# lcd13264-shield.net
KiCad netlist of a schematic drawn in EAGLE
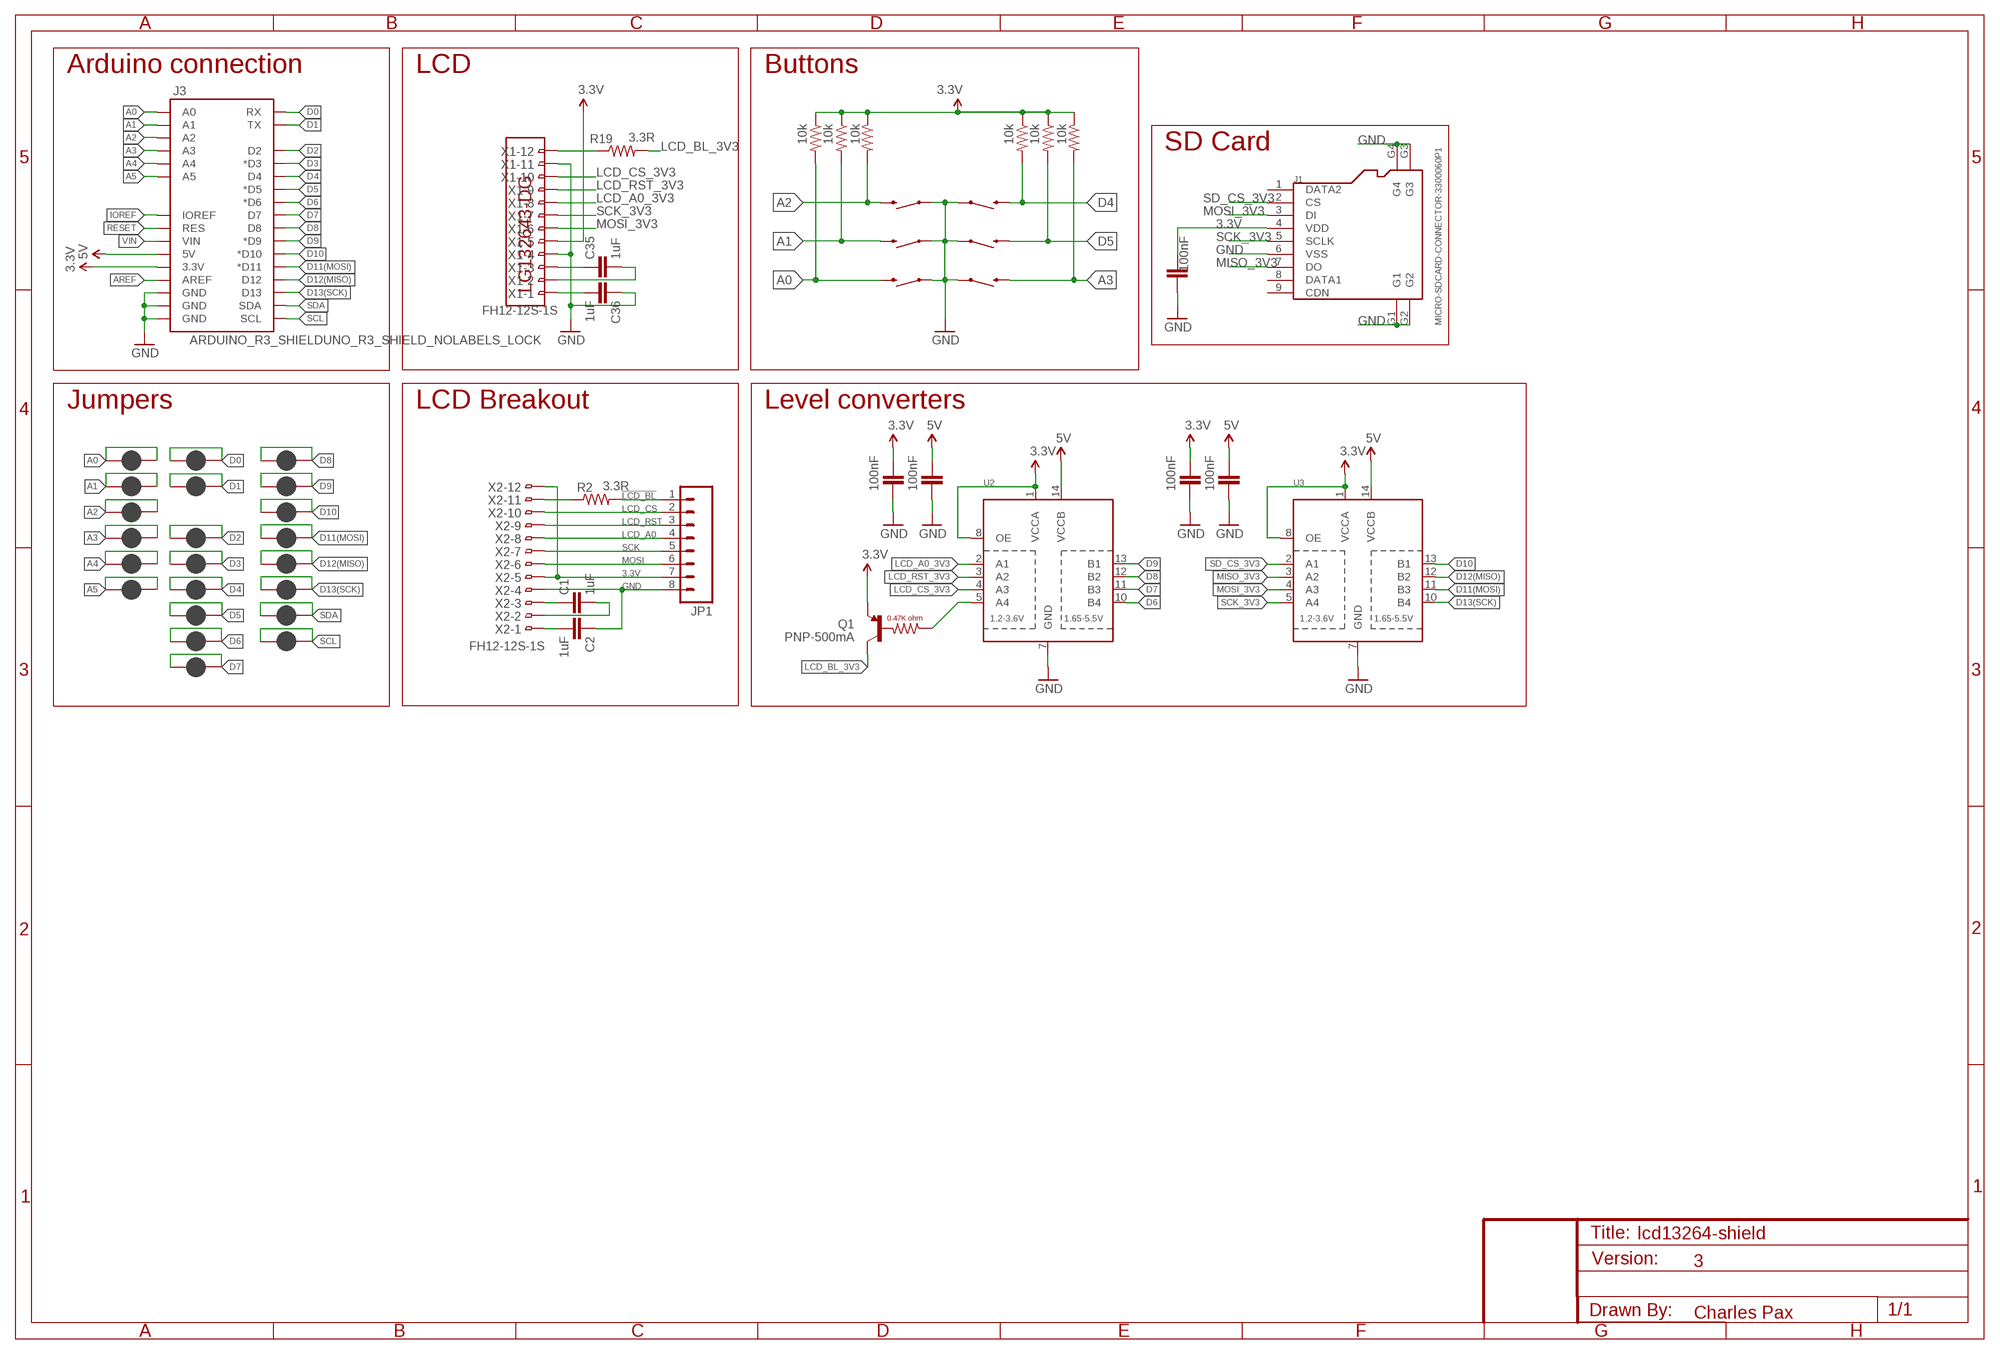
[diagram p0: schematic, sheet 1]

(export (version "E")
  (design (tool "Eeschema 10.0.6"))
  (components
    (comp (ref "C1")
      (value "1uF")
      (footprint "eagle-import:SPARKFUN-CAPACITORS_0603-CAP")
      (fields (field (name "MPN") "LMK107B7105KA-T"))
      (libsource (lib "eagle-import") (part "SPARKFUN-CAPACITORS_CAP0603-CAP"))
    )
    (comp (ref "C2")
      (value "1uF")
      (footprint "eagle-import:SPARKFUN-CAPACITORS_0603-CAP")
      (fields (field (name "MPN") "LMK107B7105KA-T"))
      (libsource (lib "eagle-import") (part "SPARKFUN-CAPACITORS_CAP0603-CAP"))
    )
    (comp (ref "C3")
      (value "100nF")
      (footprint "eagle-import:SPARKFUN-CAPACITORS_0603-CAP")
      (fields (field (name "MPN") "CL10B104KO8NNNC"))
      (libsource (lib "eagle-import") (part "SPARKFUN-CAPACITORS_CAP0603-CAP"))
    )
    (comp (ref "C4")
      (value "100nF")
      (footprint "eagle-import:SPARKFUN-CAPACITORS_0603-CAP")
      (fields (field (name "MPN") "CL10B104KO8NNNC"))
      (libsource (lib "eagle-import") (part "SPARKFUN-CAPACITORS_CAP0603-CAP"))
    )
    (comp (ref "C5")
      (value "100nF")
      (footprint "eagle-import:SPARKFUN-CAPACITORS_0603-CAP")
      (fields (field (name "MPN") "CL10B104KO8NNNC"))
      (libsource (lib "eagle-import") (part "SPARKFUN-CAPACITORS_CAP0603-CAP"))
    )
    (comp (ref "C6")
      (value "100nF")
      (footprint "eagle-import:SPARKFUN-CAPACITORS_0603-CAP")
      (fields (field (name "MPN") "CL10B104KO8NNNC"))
      (libsource (lib "eagle-import") (part "SPARKFUN-CAPACITORS_CAP0603-CAP"))
    )
    (comp (ref "C21")
      (value "100nF")
      (footprint "eagle-import:SPARKFUN-CAPACITORS_0603-CAP")
      (fields (field (name "MPN") "CL10B104KO8NNNC"))
      (libsource (lib "eagle-import") (part "SPARKFUN-CAPACITORS_CAP0603-CAP"))
    )
    (comp (ref "C35")
      (value "1uF")
      (footprint "eagle-import:SPARKFUN-CAPACITORS_0603-CAP")
      (fields (field (name "MPN") "LMK107B7105KA-T"))
      (libsource (lib "eagle-import") (part "SPARKFUN-CAPACITORS_CAP0603-CAP"))
    )
    (comp (ref "C36")
      (value "1uF")
      (footprint "eagle-import:SPARKFUN-CAPACITORS_0603-CAP")
      (fields (field (name "MPN") "LMK107B7105KA-T"))
      (libsource (lib "eagle-import") (part "SPARKFUN-CAPACITORS_CAP0603-CAP"))
    )
    (comp (ref "J1")
      (value "MICRO-SDCARD-CONNECTOR-3300060P1")
      (footprint "eagle-import:9P-SMD-W-RING")
      (libsource (lib "eagle-import") (part "MICRO-SDCARD-CONNECTOR-3300060P1"))
    )
    (comp (ref "J3")
      (value "ARDUINO_R3_SHIELDUNO_R3_SHIELD_NOLABELS_LOCK")
      (footprint "eagle-import:UNO_R3_SHIELD_NOLABELS_LOCK")
      (libsource (lib "eagle-import") (part "ARDUINO_R3_SHIELDUNO_R3_SHIELD_NOLABELS_LOCK"))
    )
    (comp (ref "JP1")
      (value "M08")
      (footprint "eagle-import:1X08_ROUND")
      (libsource (lib "eagle-import") (part "M08"))
    )
    (comp (ref "Q1")
      (value "PNP-500mA")
      (footprint "eagle-import:SOT23-3")
      (fields (field (name "MPN") "DDTB142TC"))
      (libsource (lib "eagle-import") (part "TRANSISTOR-PNP-DDTB142TC"))
    )
    (comp (ref "R1")
      (value "10k")
      (footprint "eagle-import:SPARKFUN-RESISTORS_0603-RES")
      (fields (field (name "MPN") "RC1608J103CS"))
      (libsource (lib "eagle-import") (part "SPARKFUN-RESISTORS_RESISTOR0603-RES"))
    )
    (comp (ref "R2")
      (value "3.3R")
      (footprint "eagle-import:SPARKFUN-RESISTORS_0603-RES")
      (libsource (lib "eagle-import") (part "SPARKFUN-RESISTORS_RESISTOR0603-RES"))
    )
    (comp (ref "R8")
      (value "10k")
      (footprint "eagle-import:SPARKFUN-RESISTORS_0603-RES")
      (fields (field (name "MPN") "RC1608J103CS"))
      (libsource (lib "eagle-import") (part "SPARKFUN-RESISTORS_RESISTOR0603-RES"))
    )
    (comp (ref "R11")
      (value "10k")
      (footprint "eagle-import:SPARKFUN-RESISTORS_0603-RES")
      (fields (field (name "MPN") "RC1608J103CS"))
      (libsource (lib "eagle-import") (part "SPARKFUN-RESISTORS_RESISTOR0603-RES"))
    )
    (comp (ref "R12")
      (value "10k")
      (footprint "eagle-import:SPARKFUN-RESISTORS_0603-RES")
      (fields (field (name "MPN") "RC1608J103CS"))
      (libsource (lib "eagle-import") (part "SPARKFUN-RESISTORS_RESISTOR0603-RES"))
    )
    (comp (ref "R15")
      (value "10k")
      (footprint "eagle-import:SPARKFUN-RESISTORS_0603-RES")
      (fields (field (name "MPN") "RC1608J103CS"))
      (libsource (lib "eagle-import") (part "SPARKFUN-RESISTORS_RESISTOR0603-RES"))
    )
    (comp (ref "R16")
      (value "10k")
      (footprint "eagle-import:SPARKFUN-RESISTORS_0603-RES")
      (fields (field (name "MPN") "RC1608J103CS"))
      (libsource (lib "eagle-import") (part "SPARKFUN-RESISTORS_RESISTOR0603-RES"))
    )
    (comp (ref "R19")
      (value "3.3R")
      (footprint "eagle-import:SPARKFUN-RESISTORS_0603-RES")
      (libsource (lib "eagle-import") (part "SPARKFUN-RESISTORS_RESISTOR0603-RES"))
    )
    (comp (ref "S1")
      (value "SWITCH-MOMENTARY-2SMD")
      (footprint "eagle-import:TACTILE_SWITCH_SMD")
      (libsource (lib "eagle-import") (part "SWITCH-MOMENTARY-2SMD"))
    )
    (comp (ref "S2")
      (value "SWITCH-MOMENTARY-2SMD")
      (footprint "eagle-import:TACTILE_SWITCH_SMD")
      (libsource (lib "eagle-import") (part "SWITCH-MOMENTARY-2SMD"))
    )
    (comp (ref "S3")
      (value "SWITCH-MOMENTARY-2SMD")
      (footprint "eagle-import:TACTILE_SWITCH_SMD")
      (libsource (lib "eagle-import") (part "SWITCH-MOMENTARY-2SMD"))
    )
    (comp (ref "S4")
      (value "SWITCH-MOMENTARY-2SMD")
      (footprint "eagle-import:TACTILE_SWITCH_SMD")
      (libsource (lib "eagle-import") (part "SWITCH-MOMENTARY-2SMD"))
    )
    (comp (ref "S5")
      (value "SWITCH-MOMENTARY-2SMD")
      (footprint "eagle-import:TACTILE_SWITCH_SMD")
      (libsource (lib "eagle-import") (part "SWITCH-MOMENTARY-2SMD"))
    )
    (comp (ref "S6")
      (value "SWITCH-MOMENTARY-2SMD")
      (footprint "eagle-import:TACTILE_SWITCH_SMD")
      (libsource (lib "eagle-import") (part "SWITCH-MOMENTARY-2SMD"))
    )
    (comp (ref "SJ1")
      (value "JUMPER-PAD-2-NC_BY_PASTE")
      (footprint "eagle-import:PAD-JUMPER-2-NC_BY_PASTE_YES_SILK")
      (libsource (lib "eagle-import") (part "JUMPER-PAD-2-NC_BY_PASTE"))
    )
    (comp (ref "SJ2")
      (value "JUMPER-PAD-2-NC_BY_PASTE")
      (footprint "eagle-import:PAD-JUMPER-2-NC_BY_PASTE_YES_SILK")
      (libsource (lib "eagle-import") (part "JUMPER-PAD-2-NC_BY_PASTE"))
    )
    (comp (ref "SJ3")
      (value "JUMPER-PAD-2-NC_BY_PASTE")
      (footprint "eagle-import:PAD-JUMPER-2-NC_BY_PASTE_YES_SILK")
      (libsource (lib "eagle-import") (part "JUMPER-PAD-2-NC_BY_PASTE"))
    )
    (comp (ref "SJ4")
      (value "JUMPER-PAD-2-NC_BY_PASTE")
      (footprint "eagle-import:PAD-JUMPER-2-NC_BY_PASTE_YES_SILK")
      (libsource (lib "eagle-import") (part "JUMPER-PAD-2-NC_BY_PASTE"))
    )
    (comp (ref "SJ5")
      (value "JUMPER-PAD-2-NC_BY_PASTE")
      (footprint "eagle-import:PAD-JUMPER-2-NC_BY_PASTE_YES_SILK")
      (libsource (lib "eagle-import") (part "JUMPER-PAD-2-NC_BY_PASTE"))
    )
    (comp (ref "SJ6")
      (value "JUMPER-PAD-2-NC_BY_PASTE")
      (footprint "eagle-import:PAD-JUMPER-2-NC_BY_PASTE_YES_SILK")
      (libsource (lib "eagle-import") (part "JUMPER-PAD-2-NC_BY_PASTE"))
    )
    (comp (ref "SJ7")
      (value "JUMPER-PAD-2-NC_BY_PASTE")
      (footprint "eagle-import:PAD-JUMPER-2-NC_BY_PASTE_YES_SILK")
      (libsource (lib "eagle-import") (part "JUMPER-PAD-2-NC_BY_PASTE"))
    )
    (comp (ref "SJ8")
      (value "JUMPER-PAD-2-NC_BY_PASTE")
      (footprint "eagle-import:PAD-JUMPER-2-NC_BY_PASTE_YES_SILK")
      (libsource (lib "eagle-import") (part "JUMPER-PAD-2-NC_BY_PASTE"))
    )
    (comp (ref "SJ9")
      (value "JUMPER-PAD-2-NC_BY_PASTE")
      (footprint "eagle-import:PAD-JUMPER-2-NC_BY_PASTE_YES_SILK")
      (libsource (lib "eagle-import") (part "JUMPER-PAD-2-NC_BY_PASTE"))
    )
    (comp (ref "SJ10")
      (value "JUMPER-PAD-2-NC_BY_PASTE")
      (footprint "eagle-import:PAD-JUMPER-2-NC_BY_PASTE_YES_SILK")
      (libsource (lib "eagle-import") (part "JUMPER-PAD-2-NC_BY_PASTE"))
    )
    (comp (ref "SJ11")
      (value "JUMPER-PAD-2-NC_BY_PASTE")
      (footprint "eagle-import:PAD-JUMPER-2-NC_BY_PASTE_YES_SILK")
      (libsource (lib "eagle-import") (part "JUMPER-PAD-2-NC_BY_PASTE"))
    )
    (comp (ref "SJ12")
      (value "JUMPER-PAD-2-NC_BY_PASTE")
      (footprint "eagle-import:PAD-JUMPER-2-NC_BY_PASTE_YES_SILK")
      (libsource (lib "eagle-import") (part "JUMPER-PAD-2-NC_BY_PASTE"))
    )
    (comp (ref "SJ13")
      (value "JUMPER-PAD-2-NC_BY_PASTE")
      (footprint "eagle-import:PAD-JUMPER-2-NC_BY_PASTE_YES_SILK")
      (libsource (lib "eagle-import") (part "JUMPER-PAD-2-NC_BY_PASTE"))
    )
    (comp (ref "SJ14")
      (value "JUMPER-PAD-2-NC_BY_PASTE")
      (footprint "eagle-import:PAD-JUMPER-2-NC_BY_PASTE_YES_SILK")
      (libsource (lib "eagle-import") (part "JUMPER-PAD-2-NC_BY_PASTE"))
    )
    (comp (ref "SJ19")
      (value "JUMPER-PAD-2-NC_BY_PASTE")
      (footprint "eagle-import:PAD-JUMPER-2-NC_BY_PASTE_YES_SILK")
      (libsource (lib "eagle-import") (part "JUMPER-PAD-2-NC_BY_PASTE"))
    )
    (comp (ref "SJ20")
      (value "JUMPER-PAD-2-NC_BY_PASTE")
      (footprint "eagle-import:PAD-JUMPER-2-NC_BY_PASTE_YES_SILK")
      (libsource (lib "eagle-import") (part "JUMPER-PAD-2-NC_BY_PASTE"))
    )
    (comp (ref "SJ21")
      (value "JUMPER-PAD-2-NC_BY_PASTE")
      (footprint "eagle-import:PAD-JUMPER-2-NC_BY_PASTE_YES_SILK")
      (libsource (lib "eagle-import") (part "JUMPER-PAD-2-NC_BY_PASTE"))
    )
    (comp (ref "SJ22")
      (value "JUMPER-PAD-2-NC_BY_PASTE")
      (footprint "eagle-import:PAD-JUMPER-2-NC_BY_PASTE_YES_SILK")
      (libsource (lib "eagle-import") (part "JUMPER-PAD-2-NC_BY_PASTE"))
    )
    (comp (ref "SJ23")
      (value "JUMPER-PAD-2-NC_BY_PASTE")
      (footprint "eagle-import:PAD-JUMPER-2-NC_BY_PASTE_YES_SILK")
      (libsource (lib "eagle-import") (part "JUMPER-PAD-2-NC_BY_PASTE"))
    )
    (comp (ref "SJ24")
      (value "JUMPER-PAD-2-NC_BY_PASTE")
      (footprint "eagle-import:PAD-JUMPER-2-NC_BY_PASTE_YES_SILK")
      (libsource (lib "eagle-import") (part "JUMPER-PAD-2-NC_BY_PASTE"))
    )
    (comp (ref "SJ25")
      (value "JUMPER-PAD-2-NC_BY_PASTE")
      (footprint "eagle-import:PAD-JUMPER-2-NC_BY_PASTE_YES_SILK")
      (libsource (lib "eagle-import") (part "JUMPER-PAD-2-NC_BY_PASTE"))
    )
    (comp (ref "SJ26")
      (value "JUMPER-PAD-2-NC_BY_PASTE")
      (footprint "eagle-import:PAD-JUMPER-2-NC_BY_PASTE_YES_SILK")
      (libsource (lib "eagle-import") (part "JUMPER-PAD-2-NC_BY_PASTE"))
    )
    (comp (ref "U$5")
      (value "LG132643-DG")
      (footprint "eagle-import:LG132643-DG")
      (fields (field (name "MPN") "LG132643-DW"))
      (libsource (lib "eagle-import") (part "LG132643-DG"))
    )
    (comp (ref "U2")
      (value "TXB0104PWRSOIC14")
      (footprint "eagle-import:SO14")
      (fields (field (name "MPN") "TXB0104DR"))
      (libsource (lib "eagle-import") (part "TXB0104PWRSOIC14"))
    )
    (comp (ref "U3")
      (value "TXB0104PWRSOIC14")
      (footprint "eagle-import:SO14")
      (fields (field (name "MPN") "TXB0104DR"))
      (libsource (lib "eagle-import") (part "TXB0104PWRSOIC14"))
    )
    (comp (ref "X1")
      (value "FH12-12S-1S")
      (footprint "eagle-import:FH12-12S-1SH")
      (libsource (lib "eagle-import") (part "FH12-12S-1S"))
    )
    (comp (ref "X2")
      (value "FH12-12S-1S")
      (footprint "eagle-import:FH12-12S-1SH")
      (libsource (lib "eagle-import") (part "FH12-12S-1S"))
    )
  )
  (nets
    (net (code "1") (name "3.3V") (class "Default")
      (node (ref "C21") (pin "2") (pinfunction "2_2") (pintype "passive"))
      (node (ref "C3") (pin "2") (pinfunction "2_2") (pintype "passive"))
      (node (ref "C5") (pin "2") (pinfunction "2_2") (pintype "passive"))
      (node (ref "J1") (pin "4") (pinfunction "VDD_4") (pintype "bidirectional"))
      (node (ref "J3") (pin "3.3V") (pinfunction "3.3V_3.3V") (pintype "bidirectional"))
      (node (ref "Q1") (pin "2") (pinfunction "E_2") (pintype "passive"))
      (node (ref "R1") (pin "1") (pinfunction "1_1") (pintype "passive"))
      (node (ref "R11") (pin "1") (pinfunction "1_1") (pintype "passive"))
      (node (ref "R12") (pin "1") (pinfunction "1_1") (pintype "passive"))
      (node (ref "R15") (pin "1") (pinfunction "1_1") (pintype "passive"))
      (node (ref "R16") (pin "1") (pinfunction "1_1") (pintype "passive"))
      (node (ref "R8") (pin "1") (pinfunction "1_1") (pintype "passive"))
      (node (ref "U2") (pin "1") (pinfunction "VCCA_1") (pintype "bidirectional"))
      (node (ref "U2") (pin "8") (pinfunction "OE_8") (pintype "bidirectional"))
      (node (ref "U3") (pin "1") (pinfunction "VCCA_1") (pintype "bidirectional"))
      (node (ref "U3") (pin "8") (pinfunction "OE_8") (pintype "bidirectional"))
      (node (ref "X1") (pin "5") (pinfunction "1_5") (pintype "passive"))
    )
    (net (code "2") (name "5V") (class "Default")
      (node (ref "C4") (pin "2") (pinfunction "2_2") (pintype "passive"))
      (node (ref "C6") (pin "2") (pinfunction "2_2") (pintype "passive"))
      (node (ref "J3") (pin "5V") (pinfunction "5V_5V") (pintype "bidirectional"))
      (node (ref "U2") (pin "14") (pinfunction "VCCB_14") (pintype "bidirectional"))
      (node (ref "U3") (pin "14") (pinfunction "VCCB_14") (pintype "bidirectional"))
    )
    (net (code "3") (name "A0") (class "Default")
      (node (ref "J3") (pin "A0") (pinfunction "A0_A0") (pintype "bidirectional"))
      (node (ref "R1") (pin "2") (pinfunction "2_2") (pintype "passive"))
      (node (ref "S6") (pin "3") (pinfunction "2_3") (pintype "passive"))
      (node (ref "SJ10") (pin "1") (pinfunction "1_1") (pintype "passive"))
      (node (ref "SJ10") (pin "2") (pinfunction "2_2") (pintype "passive"))
    )
    (net (code "4") (name "A1") (class "Default")
      (node (ref "J3") (pin "A1") (pinfunction "A1_A1") (pintype "bidirectional"))
      (node (ref "R16") (pin "2") (pinfunction "2_2") (pintype "passive"))
      (node (ref "S5") (pin "3") (pinfunction "2_3") (pintype "passive"))
      (node (ref "SJ7") (pin "1") (pinfunction "1_1") (pintype "passive"))
      (node (ref "SJ7") (pin "2") (pinfunction "2_2") (pintype "passive"))
    )
    (net (code "5") (name "A2") (class "Default")
      (node (ref "J3") (pin "A2") (pinfunction "A2_A2") (pintype "bidirectional"))
      (node (ref "R15") (pin "2") (pinfunction "2_2") (pintype "passive"))
      (node (ref "S4") (pin "3") (pinfunction "2_3") (pintype "passive"))
      (node (ref "SJ11") (pin "1") (pinfunction "1_1") (pintype "passive"))
      (node (ref "SJ11") (pin "2") (pinfunction "2_2") (pintype "passive"))
    )
    (net (code "6") (name "A3") (class "Default")
      (node (ref "J3") (pin "A3") (pinfunction "A3_A3") (pintype "bidirectional"))
      (node (ref "R12") (pin "2") (pinfunction "2_2") (pintype "passive"))
      (node (ref "S1") (pin "3") (pinfunction "2_3") (pintype "passive"))
      (node (ref "SJ12") (pin "1") (pinfunction "1_1") (pintype "passive"))
      (node (ref "SJ12") (pin "2") (pinfunction "2_2") (pintype "passive"))
    )
    (net (code "7") (name "A4") (class "Default")
      (node (ref "J3") (pin "A4") (pinfunction "A4_A4") (pintype "bidirectional"))
      (node (ref "SJ13") (pin "1") (pinfunction "1_1") (pintype "passive"))
      (node (ref "SJ13") (pin "2") (pinfunction "2_2") (pintype "passive"))
    )
    (net (code "8") (name "A5") (class "Default")
      (node (ref "J3") (pin "A5") (pinfunction "A5_A5") (pintype "bidirectional"))
      (node (ref "SJ14") (pin "1") (pinfunction "1_1") (pintype "passive"))
      (node (ref "SJ14") (pin "2") (pinfunction "2_2") (pintype "passive"))
    )
    (net (code "9") (name "AREF") (class "Default")
      (node (ref "J3") (pin "AREF") (pinfunction "AREF_AREF") (pintype "bidirectional"))
    )
    (net (code "10") (name "D0") (class "Default")
      (node (ref "J3") (pin "RX") (pinfunction "RX_RX") (pintype "bidirectional"))
      (node (ref "SJ8") (pin "1") (pinfunction "1_1") (pintype "passive"))
      (node (ref "SJ8") (pin "2") (pinfunction "2_2") (pintype "passive"))
    )
    (net (code "11") (name "D1") (class "Default")
      (node (ref "J3") (pin "TX") (pinfunction "TX_TX") (pintype "bidirectional"))
      (node (ref "SJ9") (pin "1") (pinfunction "1_1") (pintype "passive"))
      (node (ref "SJ9") (pin "2") (pinfunction "2_2") (pintype "passive"))
    )
    (net (code "12") (name "D2") (class "Default")
      (node (ref "J3") (pin "D2") (pinfunction "D2_D2") (pintype "bidirectional"))
      (node (ref "SJ3") (pin "1") (pinfunction "1_1") (pintype "passive"))
      (node (ref "SJ3") (pin "2") (pinfunction "2_2") (pintype "passive"))
    )
    (net (code "13") (name "D3") (class "Default")
      (node (ref "J3") (pin "D3") (pinfunction "*D3_D3") (pintype "bidirectional"))
      (node (ref "SJ4") (pin "1") (pinfunction "1_1") (pintype "passive"))
      (node (ref "SJ4") (pin "2") (pinfunction "2_2") (pintype "passive"))
    )
    (net (code "14") (name "D4") (class "Default")
      (node (ref "J3") (pin "D4") (pinfunction "D4_D4") (pintype "bidirectional"))
      (node (ref "R8") (pin "2") (pinfunction "2_2") (pintype "passive"))
      (node (ref "S3") (pin "3") (pinfunction "2_3") (pintype "passive"))
      (node (ref "SJ5") (pin "1") (pinfunction "1_1") (pintype "passive"))
      (node (ref "SJ5") (pin "2") (pinfunction "2_2") (pintype "passive"))
    )
    (net (code "15") (name "D5") (class "Default")
      (node (ref "J3") (pin "D5") (pinfunction "*D5_D5") (pintype "bidirectional"))
      (node (ref "R11") (pin "2") (pinfunction "2_2") (pintype "passive"))
      (node (ref "S2") (pin "3") (pinfunction "2_3") (pintype "passive"))
      (node (ref "SJ6") (pin "1") (pinfunction "1_1") (pintype "passive"))
      (node (ref "SJ6") (pin "2") (pinfunction "2_2") (pintype "passive"))
    )
    (net (code "16") (name "D6") (class "Default")
      (node (ref "J3") (pin "D6") (pinfunction "*D6_D6") (pintype "bidirectional"))
      (node (ref "SJ19") (pin "1") (pinfunction "1_1") (pintype "passive"))
      (node (ref "SJ19") (pin "2") (pinfunction "2_2") (pintype "passive"))
      (node (ref "U2") (pin "10") (pinfunction "B4_10") (pintype "bidirectional"))
    )
    (net (code "17") (name "D7") (class "Default")
      (node (ref "J3") (pin "D7") (pinfunction "D7_D7") (pintype "bidirectional"))
      (node (ref "SJ20") (pin "1") (pinfunction "1_1") (pintype "passive"))
      (node (ref "SJ20") (pin "2") (pinfunction "2_2") (pintype "passive"))
      (node (ref "U2") (pin "11") (pinfunction "B3_11") (pintype "bidirectional"))
    )
    (net (code "18") (name "D8") (class "Default")
      (node (ref "J3") (pin "D8") (pinfunction "D8_D8") (pintype "bidirectional"))
      (node (ref "SJ21") (pin "1") (pinfunction "1_1") (pintype "passive"))
      (node (ref "SJ21") (pin "2") (pinfunction "2_2") (pintype "passive"))
      (node (ref "U2") (pin "12") (pinfunction "B2_12") (pintype "bidirectional"))
    )
    (net (code "19") (name "D9") (class "Default")
      (node (ref "J3") (pin "D9") (pinfunction "*D9_D9") (pintype "bidirectional"))
      (node (ref "SJ22") (pin "1") (pinfunction "1_1") (pintype "passive"))
      (node (ref "SJ22") (pin "2") (pinfunction "2_2") (pintype "passive"))
      (node (ref "U2") (pin "13") (pinfunction "B1_13") (pintype "bidirectional"))
    )
    (net (code "20") (name "D10") (class "Default")
      (node (ref "J3") (pin "D10") (pinfunction "*D10_D10") (pintype "bidirectional"))
      (node (ref "SJ23") (pin "1") (pinfunction "1_1") (pintype "passive"))
      (node (ref "SJ23") (pin "2") (pinfunction "2_2") (pintype "passive"))
      (node (ref "U3") (pin "13") (pinfunction "B1_13") (pintype "bidirectional"))
    )
    (net (code "21") (name "D11(MOSI)") (class "Default")
      (node (ref "J3") (pin "D11") (pinfunction "*D11_D11") (pintype "bidirectional"))
      (node (ref "SJ24") (pin "1") (pinfunction "1_1") (pintype "passive"))
      (node (ref "SJ24") (pin "2") (pinfunction "2_2") (pintype "passive"))
      (node (ref "U3") (pin "11") (pinfunction "B3_11") (pintype "bidirectional"))
    )
    (net (code "22") (name "D12(MISO)") (class "Default")
      (node (ref "J3") (pin "D12") (pinfunction "D12_D12") (pintype "bidirectional"))
      (node (ref "SJ25") (pin "1") (pinfunction "1_1") (pintype "passive"))
      (node (ref "SJ25") (pin "2") (pinfunction "2_2") (pintype "passive"))
      (node (ref "U3") (pin "12") (pinfunction "B2_12") (pintype "bidirectional"))
    )
    (net (code "23") (name "D13(SCK)") (class "Default")
      (node (ref "J3") (pin "D13") (pinfunction "D13_D13") (pintype "bidirectional"))
      (node (ref "SJ26") (pin "1") (pinfunction "1_1") (pintype "passive"))
      (node (ref "SJ26") (pin "2") (pinfunction "2_2") (pintype "passive"))
      (node (ref "U3") (pin "10") (pinfunction "B4_10") (pintype "bidirectional"))
    )
    (net (code "24") (name "GND") (class "Default")
      (node (ref "C2") (pin "1") (pinfunction "1_1") (pintype "passive"))
      (node (ref "C21") (pin "1") (pinfunction "1_1") (pintype "passive"))
      (node (ref "C3") (pin "1") (pinfunction "1_1") (pintype "passive"))
      (node (ref "C36") (pin "1") (pinfunction "1_1") (pintype "passive"))
      (node (ref "C4") (pin "1") (pinfunction "1_1") (pintype "passive"))
      (node (ref "C5") (pin "1") (pinfunction "1_1") (pintype "passive"))
      (node (ref "C6") (pin "1") (pinfunction "1_1") (pintype "passive"))
      (node (ref "J1") (pin "6") (pinfunction "VSS_6") (pintype "bidirectional"))
      (node (ref "J1") (pin "G1") (pinfunction "G1_G1") (pintype "bidirectional"))
      (node (ref "J1") (pin "G2") (pinfunction "G2_G2") (pintype "bidirectional"))
      (node (ref "J1") (pin "G3") (pinfunction "G3_G3") (pintype "bidirectional"))
      (node (ref "J1") (pin "G4") (pinfunction "G4_G4") (pintype "bidirectional"))
      (node (ref "J3") (pin "GND@0") (pinfunction "GND_GND@0") (pintype "bidirectional"))
      (node (ref "J3") (pin "GND@1") (pinfunction "GND_GND@1") (pintype "bidirectional"))
      (node (ref "J3") (pin "GND@2") (pinfunction "GND_GND@2") (pintype "bidirectional"))
      (node (ref "JP1") (pin "8") (pinfunction "8_8") (pintype "passive"))
      (node (ref "S1") (pin "1") (pinfunction "1_1") (pintype "passive"))
      (node (ref "S2") (pin "1") (pinfunction "1_1") (pintype "passive"))
      (node (ref "S3") (pin "1") (pinfunction "1_1") (pintype "passive"))
      (node (ref "S4") (pin "1") (pinfunction "1_1") (pintype "passive"))
      (node (ref "S5") (pin "1") (pinfunction "1_1") (pintype "passive"))
      (node (ref "S6") (pin "1") (pinfunction "1_1") (pintype "passive"))
      (node (ref "U2") (pin "7") (pinfunction "GND_7") (pintype "bidirectional"))
      (node (ref "U3") (pin "7") (pinfunction "GND_7") (pintype "bidirectional"))
      (node (ref "X1") (pin "11") (pinfunction "1_11") (pintype "passive"))
      (node (ref "X1") (pin "4") (pinfunction "1_4") (pintype "passive"))
      (node (ref "X2") (pin "4") (pinfunction "1_4") (pintype "passive"))
    )
    (net (code "25") (name "IOREF") (class "Default")
      (node (ref "J3") (pin "IOREF") (pinfunction "IOREF_IOREF") (pintype "bidirectional"))
    )
    (net (code "26") (name "LCD_A0_3V3") (class "Default")
      (node (ref "U2") (pin "2") (pinfunction "A1_2") (pintype "bidirectional"))
      (node (ref "X1") (pin "8") (pinfunction "1_8") (pintype "passive"))
    )
    (net (code "27") (name "LCD_BL_3V3") (class "Default")
      (node (ref "Q1") (pin "3") (pinfunction "C_3") (pintype "passive"))
      (node (ref "R19") (pin "2") (pinfunction "2_2") (pintype "passive"))
    )
    (net (code "28") (name "LCD_CS_3V3") (class "Default")
      (node (ref "U2") (pin "4") (pinfunction "A3_4") (pintype "bidirectional"))
      (node (ref "X1") (pin "10") (pinfunction "1_10") (pintype "passive"))
    )
    (net (code "29") (name "LCD_RST_3V3") (class "Default")
      (node (ref "U2") (pin "3") (pinfunction "A2_3") (pintype "bidirectional"))
      (node (ref "X1") (pin "9") (pinfunction "1_9") (pintype "passive"))
    )
    (net (code "30") (name "MISO_3V3") (class "Default")
      (node (ref "J1") (pin "7") (pinfunction "DO_7") (pintype "bidirectional"))
      (node (ref "U3") (pin "3") (pinfunction "A2_3") (pintype "bidirectional"))
    )
    (net (code "31") (name "MOSI_3V3") (class "Default")
      (node (ref "J1") (pin "3") (pinfunction "DI_3") (pintype "bidirectional"))
      (node (ref "U3") (pin "4") (pinfunction "A3_4") (pintype "bidirectional"))
      (node (ref "X1") (pin "6") (pinfunction "1_6") (pintype "passive"))
    )
    (net (code "32") (name "Net-(C2-Pad2)") (class "Default")
      (node (ref "C2") (pin "2") (pinfunction "2_2") (pintype "passive"))
      (node (ref "X2") (pin "1") (pinfunction "1_1") (pintype "passive"))
    )
    (net (code "33") (name "Net-(C36-Pad2)") (class "Default")
      (node (ref "C36") (pin "2") (pinfunction "2_2") (pintype "passive"))
      (node (ref "X1") (pin "1") (pinfunction "1_1") (pintype "passive"))
    )
    (net (code "34") (name "Net-(JP1-Pad1)") (class "Default")
      (node (ref "JP1") (pin "1") (pinfunction "1_1") (pintype "passive"))
      (node (ref "R2") (pin "2") (pinfunction "2_2") (pintype "passive"))
    )
    (net (code "35") (name "Net-(Q1-B)") (class "Default")
      (node (ref "Q1") (pin "1") (pinfunction "B_1") (pintype "passive"))
      (node (ref "U2") (pin "5") (pinfunction "A4_5") (pintype "bidirectional"))
    )
    (net (code "36") (name "Net-(X1D-1)") (class "Default")
      (node (ref "R19") (pin "1") (pinfunction "1_1") (pintype "passive"))
      (node (ref "X1") (pin "12") (pinfunction "1_12") (pintype "passive"))
    )
    (net (code "37") (name "Net-(X1E-1)") (class "Default")
      (node (ref "C35") (pin "2") (pinfunction "2_2") (pintype "passive"))
      (node (ref "X1") (pin "2") (pinfunction "1_2") (pintype "passive"))
    )
    (net (code "38") (name "Net-(X1F-1)") (class "Default")
      (node (ref "C35") (pin "1") (pinfunction "1_1") (pintype "passive"))
      (node (ref "X1") (pin "3") (pinfunction "1_3") (pintype "passive"))
    )
    (net (code "39") (name "Net-(X2B-1)") (class "Default")
      (node (ref "JP1") (pin "2") (pinfunction "2_2") (pintype "passive"))
      (node (ref "X2") (pin "10") (pinfunction "1_10") (pintype "passive"))
    )
    (net (code "40") (name "Net-(X2C-1)") (class "Default")
      (node (ref "R2") (pin "1") (pinfunction "1_1") (pintype "passive"))
      (node (ref "X2") (pin "11") (pinfunction "1_11") (pintype "passive"))
    )
    (net (code "41") (name "Net-(X2D-1)") (class "Default")
      (node (ref "JP1") (pin "7") (pinfunction "7_7") (pintype "passive"))
      (node (ref "X2") (pin "12") (pinfunction "1_12") (pintype "passive"))
      (node (ref "X2") (pin "5") (pinfunction "1_5") (pintype "passive"))
    )
    (net (code "42") (name "Net-(X2E-1)") (class "Default")
      (node (ref "C1") (pin "2") (pinfunction "2_2") (pintype "passive"))
      (node (ref "X2") (pin "2") (pinfunction "1_2") (pintype "passive"))
    )
    (net (code "43") (name "Net-(X2F-1)") (class "Default")
      (node (ref "C1") (pin "1") (pinfunction "1_1") (pintype "passive"))
      (node (ref "X2") (pin "3") (pinfunction "1_3") (pintype "passive"))
    )
    (net (code "44") (name "Net-(X2I-1)") (class "Default")
      (node (ref "JP1") (pin "6") (pinfunction "6_6") (pintype "passive"))
      (node (ref "X2") (pin "6") (pinfunction "1_6") (pintype "passive"))
    )
    (net (code "45") (name "Net-(X2J-1)") (class "Default")
      (node (ref "JP1") (pin "5") (pinfunction "5_5") (pintype "passive"))
      (node (ref "X2") (pin "7") (pinfunction "1_7") (pintype "passive"))
    )
    (net (code "46") (name "Net-(X2K-1)") (class "Default")
      (node (ref "JP1") (pin "4") (pinfunction "4_4") (pintype "passive"))
      (node (ref "X2") (pin "8") (pinfunction "1_8") (pintype "passive"))
    )
    (net (code "47") (name "Net-(X2L-1)") (class "Default")
      (node (ref "JP1") (pin "3") (pinfunction "3_3") (pintype "passive"))
      (node (ref "X2") (pin "9") (pinfunction "1_9") (pintype "passive"))
    )
    (net (code "48") (name "RESET") (class "Default")
      (node (ref "J3") (pin "RES") (pinfunction "RES_RES") (pintype "bidirectional"))
    )
    (net (code "49") (name "SCK_3V3") (class "Default")
      (node (ref "J1") (pin "5") (pinfunction "SCLK_5") (pintype "bidirectional"))
      (node (ref "U3") (pin "5") (pinfunction "A4_5") (pintype "bidirectional"))
      (node (ref "X1") (pin "7") (pinfunction "1_7") (pintype "passive"))
    )
    (net (code "50") (name "SCL") (class "Default")
      (node (ref "J3") (pin "SCL") (pinfunction "SCL_SCL") (pintype "bidirectional"))
      (node (ref "SJ2") (pin "1") (pinfunction "1_1") (pintype "passive"))
      (node (ref "SJ2") (pin "2") (pinfunction "2_2") (pintype "passive"))
    )
    (net (code "51") (name "SDA") (class "Default")
      (node (ref "J3") (pin "SDA") (pinfunction "SDA_SDA") (pintype "bidirectional"))
      (node (ref "SJ1") (pin "1") (pinfunction "1_1") (pintype "passive"))
      (node (ref "SJ1") (pin "2") (pinfunction "2_2") (pintype "passive"))
    )
    (net (code "52") (name "SD_CS_3V3") (class "Default")
      (node (ref "J1") (pin "2") (pinfunction "CS_2") (pintype "bidirectional"))
      (node (ref "U3") (pin "2") (pinfunction "A1_2") (pintype "bidirectional"))
    )
    (net (code "53") (name "VIN") (class "Default")
      (node (ref "J3") (pin "VIN") (pinfunction "VIN_VIN") (pintype "bidirectional"))
    )
    (net (code "54") (name "unconnected-(J1-CDN-Pad9)") (class "Default")
      (node (ref "J1") (pin "9") (pinfunction "CDN_9") (pintype "bidirectional"))
    )
    (net (code "55") (name "unconnected-(J1-DATA1-Pad8)") (class "Default")
      (node (ref "J1") (pin "8") (pinfunction "DATA1_8") (pintype "bidirectional"))
    )
    (net (code "56") (name "unconnected-(J1-DATA2-Pad1)") (class "Default")
      (node (ref "J1") (pin "1") (pinfunction "DATA2_1") (pintype "bidirectional"))
    )
  )
)
